# C64_KernalSw_8k.net
KiCad netlist of a schematic drawn in EAGLE
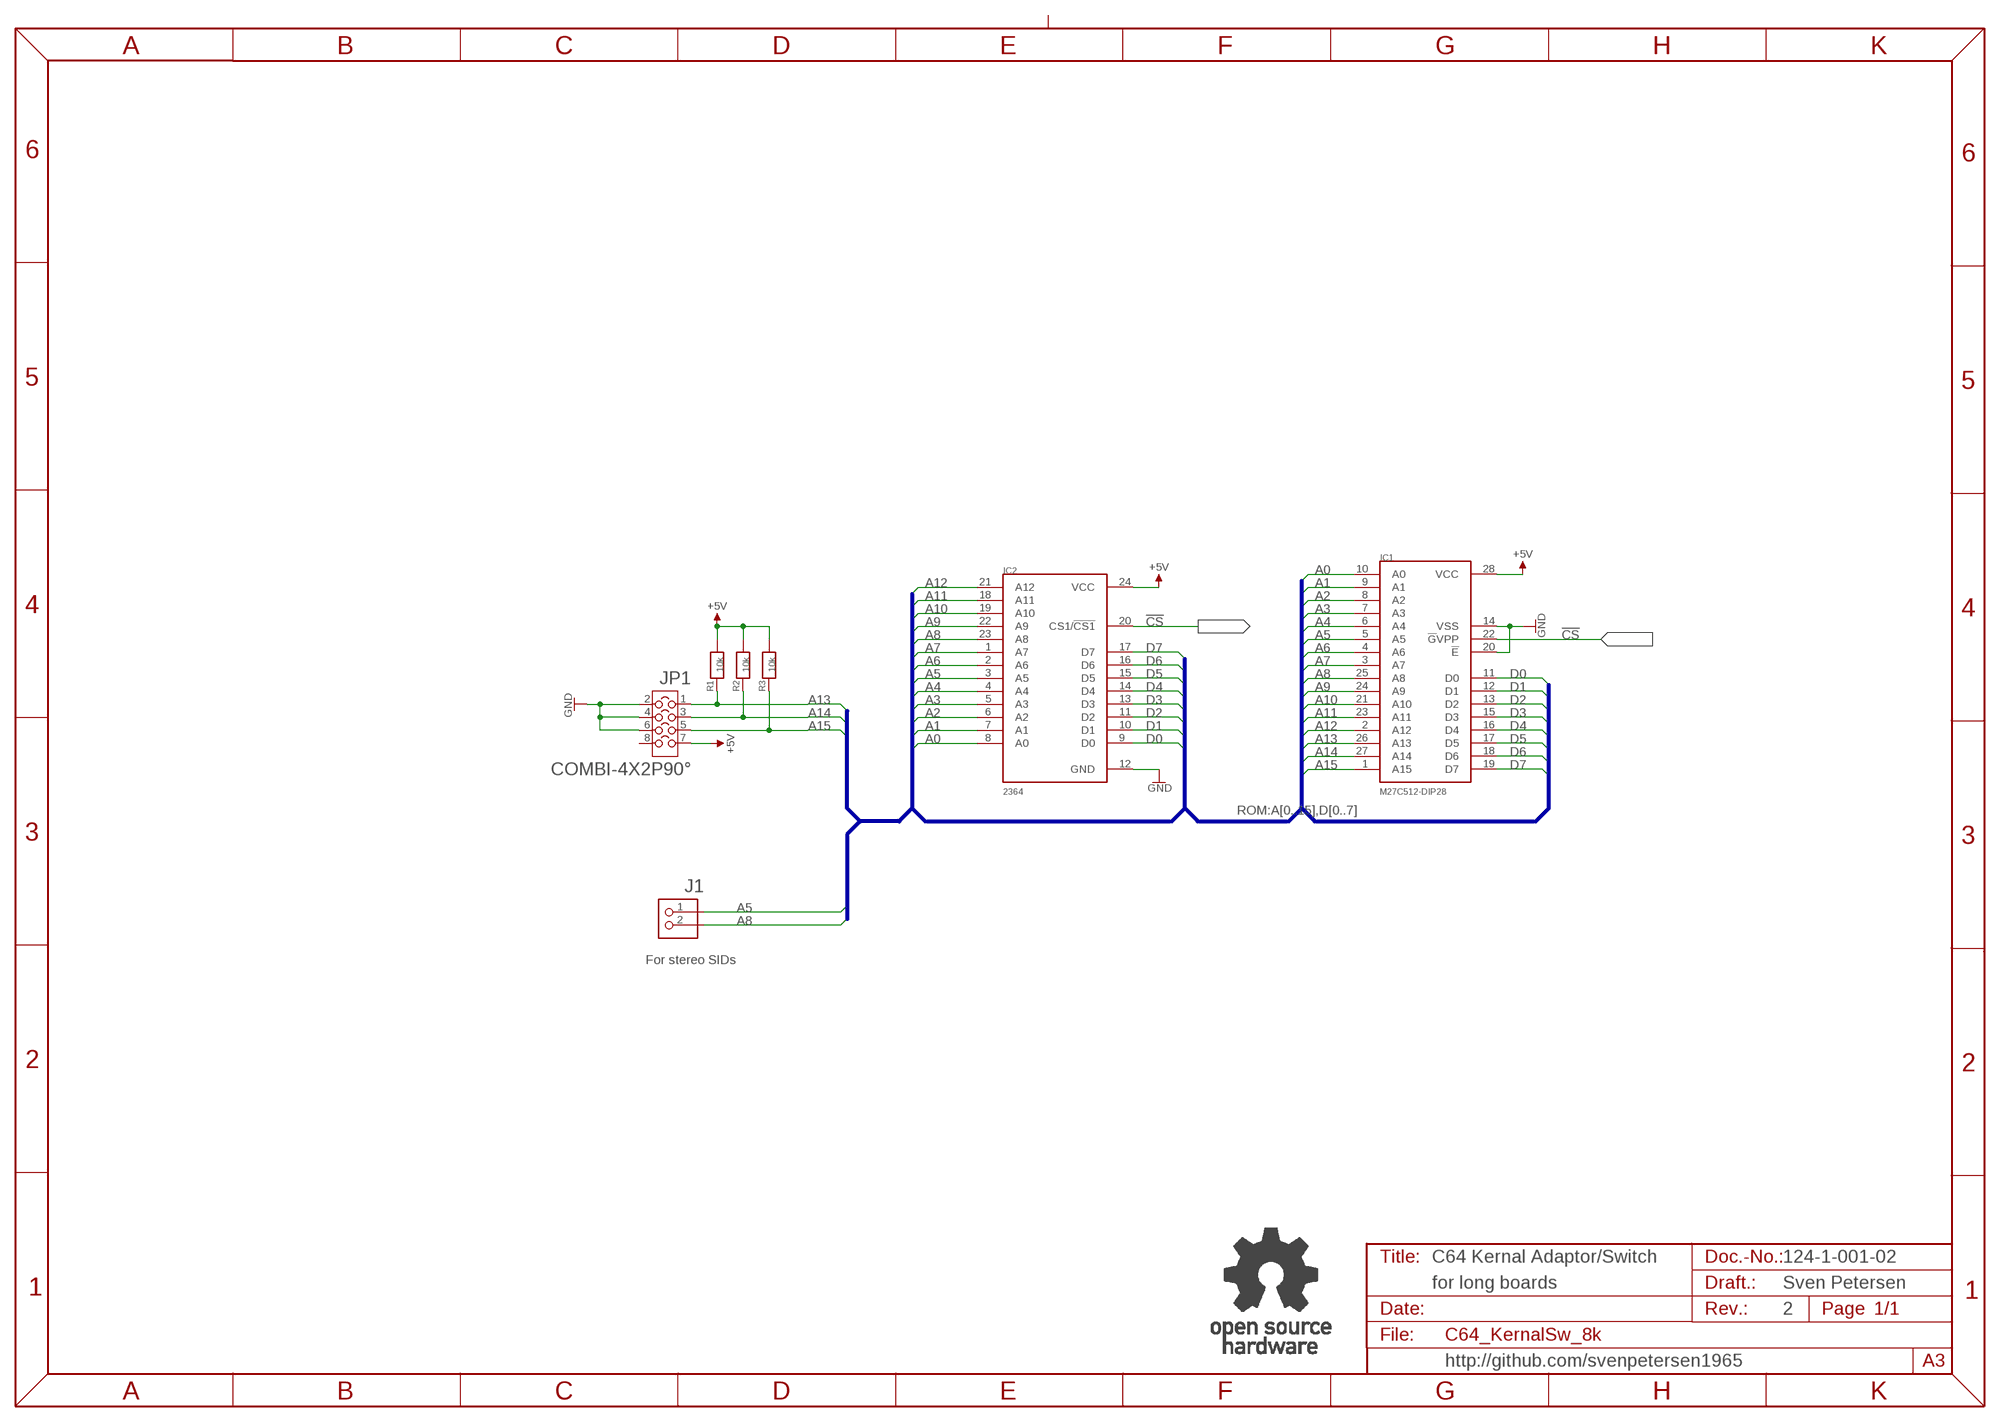
[diagram p0: schematic, sheet 1]

(export (version "E")
  (design (tool "Eeschema 10.0.6"))
  (components
    (comp (ref "IC1")
      (value "M27C512-DIP28")
      (footprint "eagle-import:DIL28-6")
      (libsource (lib "eagle-import") (part "M27C512-DIP28"))
    )
    (comp (ref "IC2")
      (value "2364")
      (footprint "eagle-import:DIL24_SOCKET")
      (libsource (lib "eagle-import") (part "2364"))
    )
    (comp (ref "J1")
      (value "PINHD-1X2")
      (footprint "eagle-import:1X02")
      (libsource (lib "eagle-import") (part "PINHD-1X2"))
    )
    (comp (ref "JP1")
      (value "COMBI-4X2P90°")
      (footprint "eagle-import:COMBI-4X2-90")
      (libsource (lib "eagle-import") (part "COMBI-4X2P90°"))
    )
    (comp (ref "R1")
      (value "10k")
      (footprint "eagle-import:0805")
      (libsource (lib "eagle-import") (part "R-0805"))
    )
    (comp (ref "R2")
      (value "10k")
      (footprint "eagle-import:0805")
      (libsource (lib "eagle-import") (part "R-0805"))
    )
    (comp (ref "R3")
      (value "10k")
      (footprint "eagle-import:0805")
      (libsource (lib "eagle-import") (part "R-0805"))
    )
    (comp (ref "U$11")
      (value "OPEN_SOURCE_HW")
      (footprint "eagle-import:OPENHW")
      (libsource (lib "eagle-import") (part "OPEN_SOURCE_HW"))
    )
  )
  (nets
    (net (code "1") (name "+5V") (class "Default")
      (node (ref "IC1") (pin "28") (pinfunction "VCC_28") (pintype "power_in"))
      (node (ref "IC2") (pin "24") (pinfunction "VCC_24") (pintype "power_in"))
      (node (ref "JP1") (pin "7") (pinfunction "7_7") (pintype "bidirectional"))
      (node (ref "R1") (pin "2") (pinfunction "2_2") (pintype "passive"))
      (node (ref "R2") (pin "2") (pinfunction "2_2") (pintype "passive"))
      (node (ref "R3") (pin "2") (pinfunction "2_2") (pintype "passive"))
    )
    (net (code "2") (name "/A0") (class "Default")
      (node (ref "IC1") (pin "10") (pinfunction "A0_10") (pintype "input"))
      (node (ref "IC2") (pin "8") (pinfunction "A0_8") (pintype "input"))
    )
    (net (code "3") (name "/A1") (class "Default")
      (node (ref "IC1") (pin "9") (pinfunction "A1_9") (pintype "input"))
      (node (ref "IC2") (pin "7") (pinfunction "A1_7") (pintype "input"))
    )
    (net (code "4") (name "/A2") (class "Default")
      (node (ref "IC1") (pin "8") (pinfunction "A2_8") (pintype "input"))
      (node (ref "IC2") (pin "6") (pinfunction "A2_6") (pintype "input"))
    )
    (net (code "5") (name "/A3") (class "Default")
      (node (ref "IC1") (pin "7") (pinfunction "A3_7") (pintype "input"))
      (node (ref "IC2") (pin "5") (pinfunction "A3_5") (pintype "input"))
    )
    (net (code "6") (name "/A4") (class "Default")
      (node (ref "IC1") (pin "6") (pinfunction "A4_6") (pintype "input"))
      (node (ref "IC2") (pin "4") (pinfunction "A4_4") (pintype "input"))
    )
    (net (code "7") (name "/A5") (class "Default")
      (node (ref "IC1") (pin "5") (pinfunction "A5_5") (pintype "input"))
      (node (ref "IC2") (pin "3") (pinfunction "A5_3") (pintype "input"))
      (node (ref "J1") (pin "1") (pinfunction "1_1") (pintype "passive"))
    )
    (net (code "8") (name "/A6") (class "Default")
      (node (ref "IC1") (pin "4") (pinfunction "A6_4") (pintype "input"))
      (node (ref "IC2") (pin "2") (pinfunction "A6_2") (pintype "input"))
    )
    (net (code "9") (name "/A7") (class "Default")
      (node (ref "IC1") (pin "3") (pinfunction "A7_3") (pintype "input"))
      (node (ref "IC2") (pin "1") (pinfunction "A7_1") (pintype "input"))
    )
    (net (code "10") (name "/A8") (class "Default")
      (node (ref "IC1") (pin "25") (pinfunction "A8_25") (pintype "input"))
      (node (ref "IC2") (pin "23") (pinfunction "A8_23") (pintype "input"))
      (node (ref "J1") (pin "2") (pinfunction "2_2") (pintype "passive"))
    )
    (net (code "11") (name "/A9") (class "Default")
      (node (ref "IC1") (pin "24") (pinfunction "A9_24") (pintype "input"))
      (node (ref "IC2") (pin "22") (pinfunction "A9_22") (pintype "input"))
    )
    (net (code "12") (name "/A10") (class "Default")
      (node (ref "IC1") (pin "21") (pinfunction "A10_21") (pintype "input"))
      (node (ref "IC2") (pin "19") (pinfunction "A10_19") (pintype "input"))
    )
    (net (code "13") (name "/A11") (class "Default")
      (node (ref "IC1") (pin "23") (pinfunction "A11_23") (pintype "input"))
      (node (ref "IC2") (pin "18") (pinfunction "A11_18") (pintype "input"))
    )
    (net (code "14") (name "/A12") (class "Default")
      (node (ref "IC1") (pin "2") (pinfunction "A12_2") (pintype "input"))
      (node (ref "IC2") (pin "21") (pinfunction "A12_21") (pintype "input"))
    )
    (net (code "15") (name "/A13") (class "Default")
      (node (ref "IC1") (pin "26") (pinfunction "A13_26") (pintype "input"))
      (node (ref "JP1") (pin "1") (pinfunction "1_1") (pintype "bidirectional"))
      (node (ref "R1") (pin "1") (pinfunction "1_1") (pintype "passive"))
    )
    (net (code "16") (name "/A14") (class "Default")
      (node (ref "IC1") (pin "27") (pinfunction "A14_27") (pintype "input"))
      (node (ref "JP1") (pin "3") (pinfunction "3_3") (pintype "bidirectional"))
      (node (ref "R2") (pin "1") (pinfunction "1_1") (pintype "passive"))
    )
    (net (code "17") (name "/A15") (class "Default")
      (node (ref "IC1") (pin "1") (pinfunction "A15_1") (pintype "input"))
      (node (ref "JP1") (pin "5") (pinfunction "5_5") (pintype "bidirectional"))
      (node (ref "R3") (pin "1") (pinfunction "1_1") (pintype "passive"))
    )
    (net (code "18") (name "/D0") (class "Default")
      (node (ref "IC1") (pin "11") (pinfunction "D0_11") (pintype "bidirectional"))
      (node (ref "IC2") (pin "9") (pinfunction "D0_9") (pintype "tri_state"))
    )
    (net (code "19") (name "/D1") (class "Default")
      (node (ref "IC1") (pin "12") (pinfunction "D1_12") (pintype "bidirectional"))
      (node (ref "IC2") (pin "10") (pinfunction "D1_10") (pintype "tri_state"))
    )
    (net (code "20") (name "/D2") (class "Default")
      (node (ref "IC1") (pin "13") (pinfunction "D2_13") (pintype "bidirectional"))
      (node (ref "IC2") (pin "11") (pinfunction "D2_11") (pintype "tri_state"))
    )
    (net (code "21") (name "/D3") (class "Default")
      (node (ref "IC1") (pin "15") (pinfunction "D3_15") (pintype "bidirectional"))
      (node (ref "IC2") (pin "13") (pinfunction "D3_13") (pintype "tri_state"))
    )
    (net (code "22") (name "/D4") (class "Default")
      (node (ref "IC1") (pin "16") (pinfunction "D4_16") (pintype "bidirectional"))
      (node (ref "IC2") (pin "14") (pinfunction "D4_14") (pintype "tri_state"))
    )
    (net (code "23") (name "/D5") (class "Default")
      (node (ref "IC1") (pin "17") (pinfunction "D5_17") (pintype "bidirectional"))
      (node (ref "IC2") (pin "15") (pinfunction "D5_15") (pintype "tri_state"))
    )
    (net (code "24") (name "/D6") (class "Default")
      (node (ref "IC1") (pin "18") (pinfunction "D6_18") (pintype "bidirectional"))
      (node (ref "IC2") (pin "16") (pinfunction "D6_16") (pintype "tri_state"))
    )
    (net (code "25") (name "/D7") (class "Default")
      (node (ref "IC1") (pin "19") (pinfunction "D7_19") (pintype "bidirectional"))
      (node (ref "IC2") (pin "17") (pinfunction "D7_17") (pintype "tri_state"))
    )
    (net (code "27") (name "/~{CS}") (class "Default")
      (node (ref "IC1") (pin "22") (pinfunction "~{G}VPP_22") (pintype "input"))
      (node (ref "IC2") (pin "20") (pinfunction "CS1/~{CS1}_20") (pintype "input"))
    )
    (net (code "28") (name "GND") (class "Default")
      (node (ref "IC1") (pin "14") (pinfunction "VSS_14") (pintype "power_in"))
      (node (ref "IC1") (pin "20") (pinfunction "~{E}_20") (pintype "input"))
      (node (ref "IC2") (pin "12") (pinfunction "GND_12") (pintype "power_in"))
      (node (ref "JP1") (pin "2") (pinfunction "2_2") (pintype "bidirectional"))
      (node (ref "JP1") (pin "4") (pinfunction "4_4") (pintype "bidirectional"))
      (node (ref "JP1") (pin "6") (pinfunction "6_6") (pintype "bidirectional"))
    )
    (net (code "29") (name "unconnected-(JP1-Pad8)") (class "Default")
      (node (ref "JP1") (pin "8") (pinfunction "8_8") (pintype "bidirectional"))
    )
  )
)
